# 40.net
KiCad netlist of a schematic drawn in Altium Designer
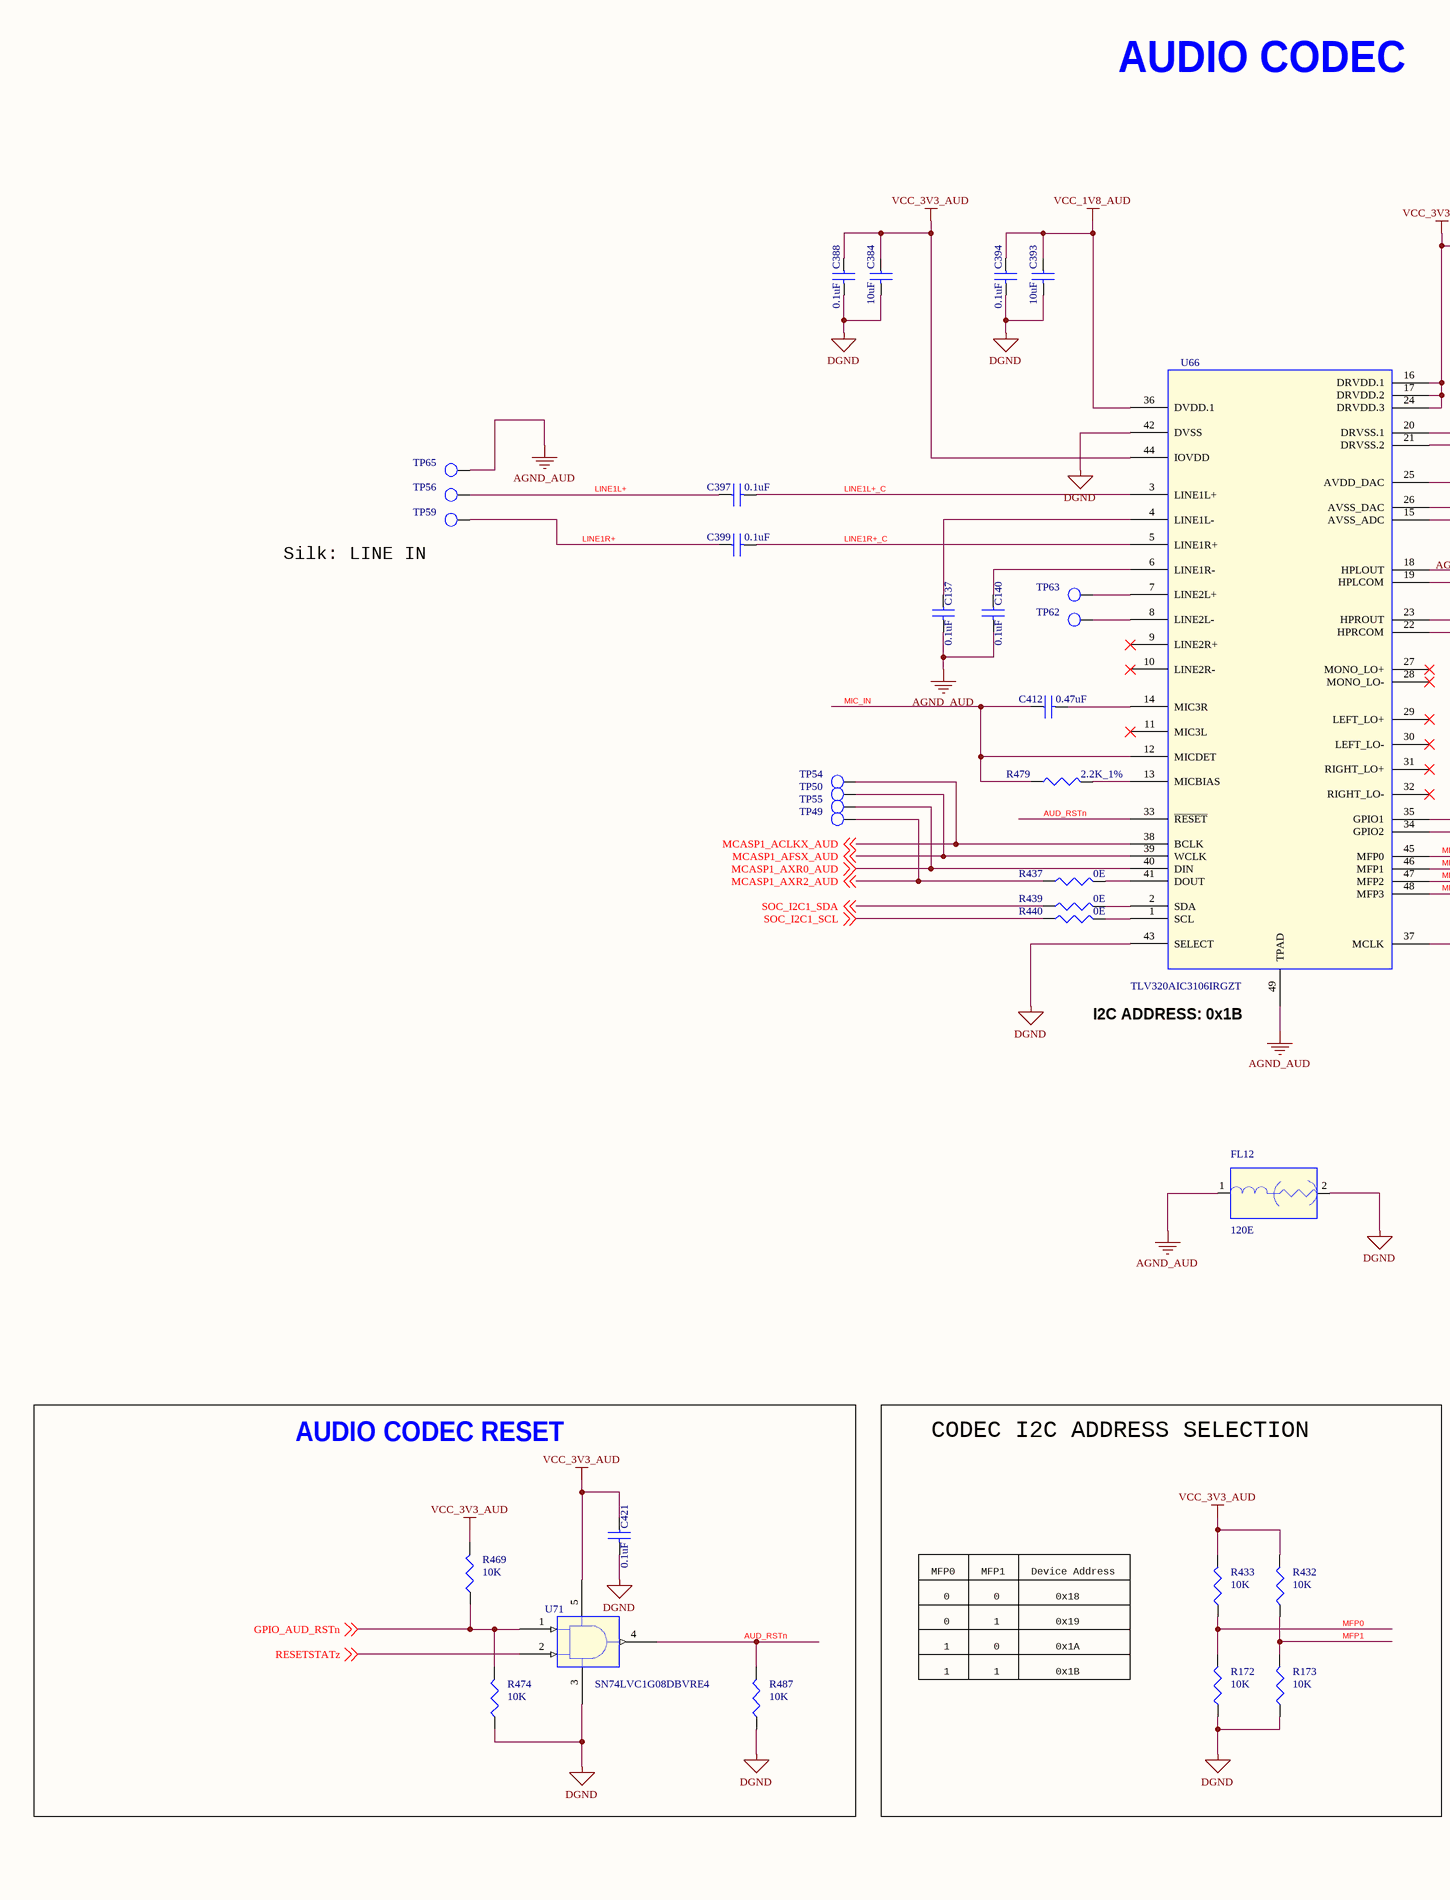
[diagram p0: 40.SchDoc, left]
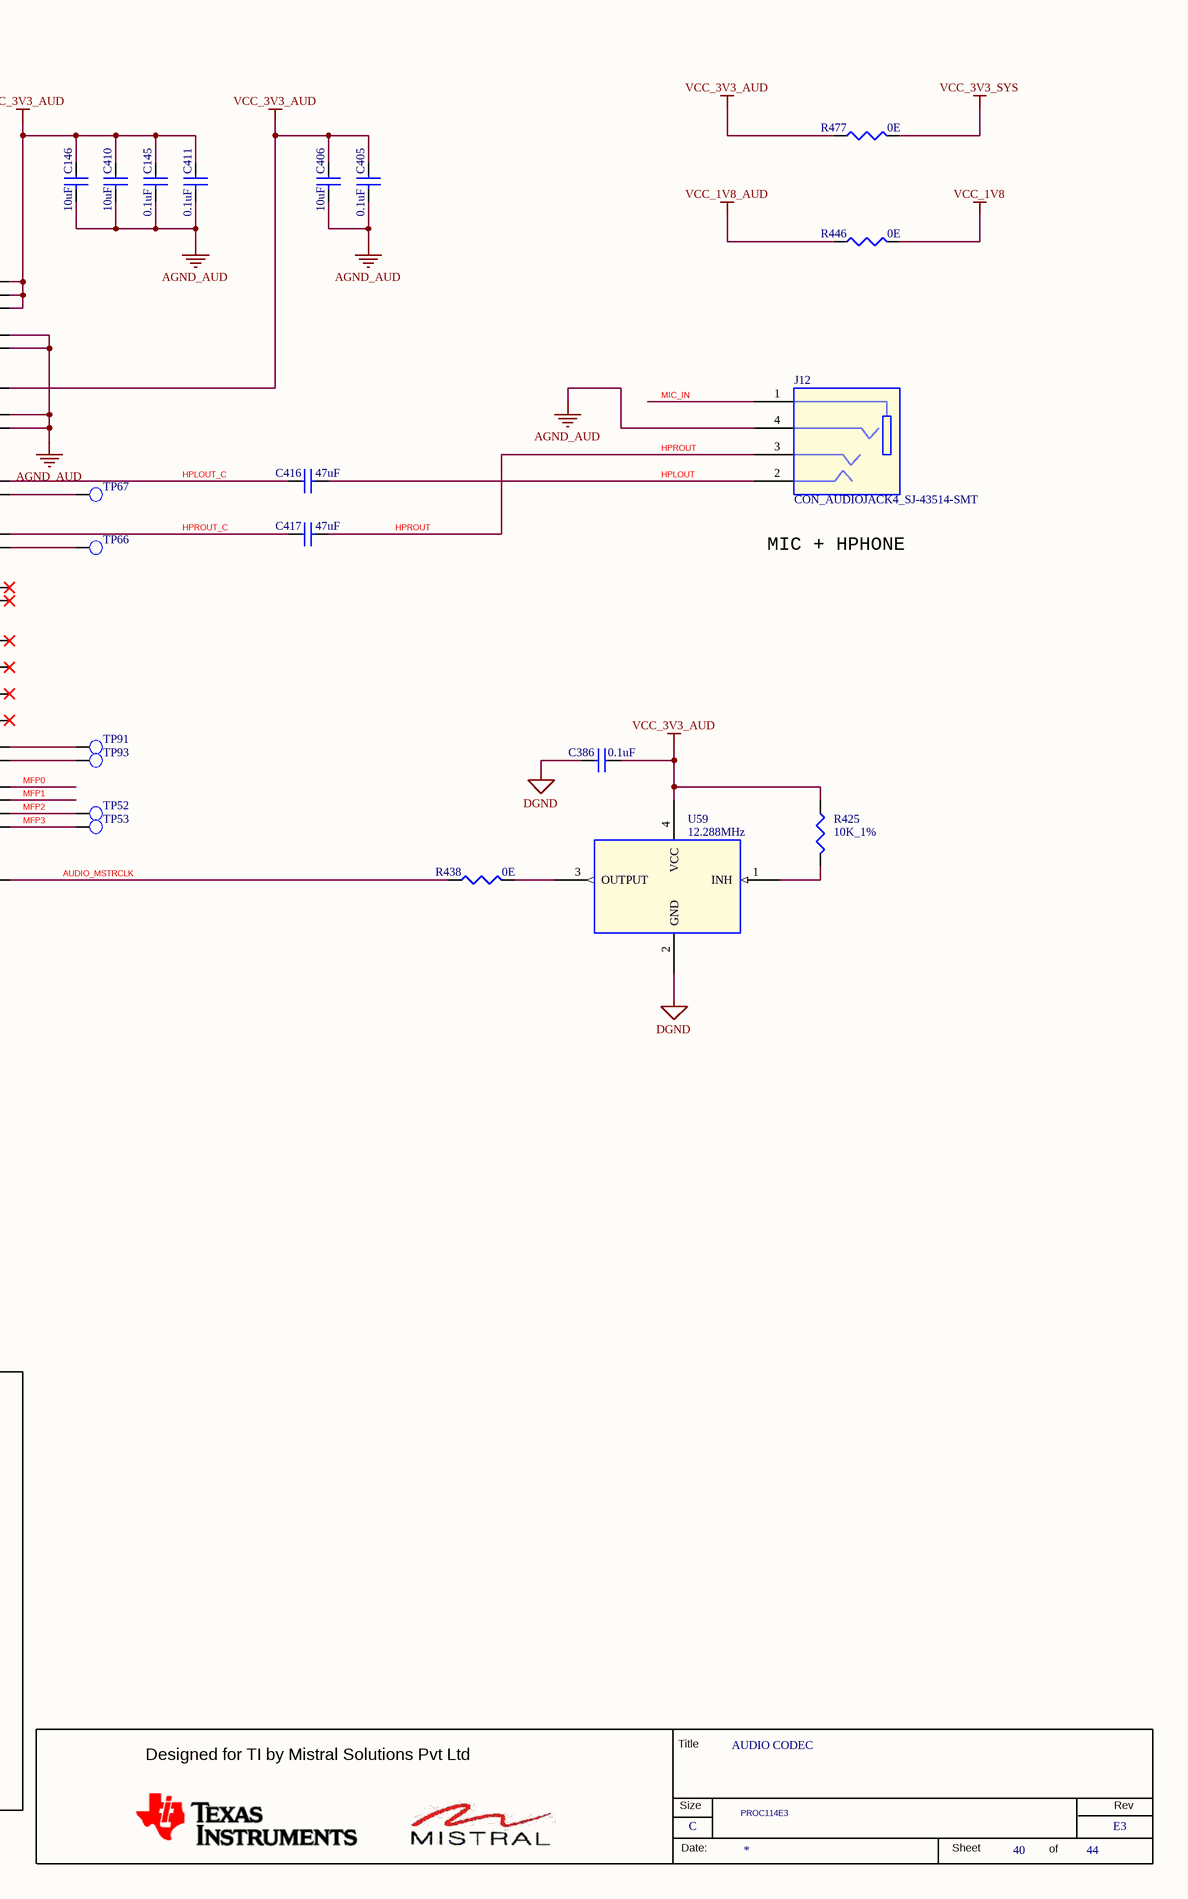
[diagram p1: 40.SchDoc, right]

(export (version "E")
  (design (tool "Eeschema 10.0.6"))
  (components
    (comp (ref "C137")
      (value "0.1uF")
      (footprint "CAP0201_0-5")
      (description "CAP CERAMIC 0.1uF 16V 10% X5R 0201")
      (fields (field (name "DISTRIBUTOR_PART_NUMBER") "490-14305-1-ND") (field (name "VOLTAGE") "16V"))
      (libsource (lib "*") (part "CAP_Dup2"))
    )
    (comp (ref "C140")
      (value "0.1uF")
      (footprint "CAP0201_0-5")
      (description "CAP CERAMIC 0.1uF 16V 10% X5R 0201")
      (fields (field (name "DISTRIBUTOR_PART_NUMBER") "490-14305-1-ND") (field (name "VOLTAGE") "16V"))
      (libsource (lib "*") (part "CAP_Dup2"))
    )
    (comp (ref "C145")
      (value "0.1uF")
      (footprint "CAP0201_0-5")
      (description "CAP CERAMIC 0.1uF 16V 10% X5R 0201")
      (fields
        (field (name "MISTRAL PART NO") "120009030072-R")
        (field (name "MFR_PART_NUMBER") "GRM033R61C104KE14D")
      )
      (libsource (lib "*") (part "CAP_Dup2"))
    )
    (comp (ref "C146")
      (value "10uF")
      (footprint "CAP0402_0-75")
      (description "CAP CERAMIC 10uF 10V 20% X5R 0402")
      (fields
        (field (name "DISTRIBUTOR_PART_NUMBER") "490-GRM155R61A106ME11DTR-ND")
        (field (name "VOLTAGE") "10V")
      )
      (libsource (lib "*") (part "CAP_Dup2"))
    )
    (comp (ref "C384")
      (value "10uF")
      (footprint "CAP0402_0-75")
      (description "CAP CERAMIC 10uF 10V 20% X5R 0402")
      (fields
        (field (name "DISTRIBUTOR_PART_NUMBER") "490-GRM155R61A106ME11DTR-ND")
        (field (name "VOLTAGE") "10V")
      )
      (libsource (lib "*") (part "CAP_Dup2"))
    )
    (comp (ref "C386")
      (value "0.1uF")
      (footprint "CAP0201_0-5")
      (description "CAP CERAMIC 0.1uF 16V 10% X5R 0201")
      (fields (field (name "DISTRIBUTOR_PART_NUMBER") "490-14305-1-ND") (field (name "VOLTAGE") "16V"))
      (libsource (lib "*") (part "CAP_Dup2"))
    )
    (comp (ref "C388")
      (value "0.1uF")
      (footprint "CAP0201_0-5")
      (description "CAP CERAMIC 0.1uF 16V 10% X5R 0201")
      (fields (field (name "DISTRIBUTOR_PART_NUMBER") "490-14305-1-ND") (field (name "VOLTAGE") "16V"))
      (libsource (lib "*") (part "CAP_Dup2"))
    )
    (comp (ref "C393")
      (value "10uF")
      (footprint "CAP0402_0-75")
      (description "CAP CERAMIC 10uF 10V 20% X5R 0402")
      (fields
        (field (name "DISTRIBUTOR_PART_NUMBER") "490-GRM155R61A106ME11DTR-ND")
        (field (name "VOLTAGE") "10V")
      )
      (libsource (lib "*") (part "CAP_Dup2"))
    )
    (comp (ref "C394")
      (value "0.1uF")
      (footprint "CAP0201_0-5")
      (description "CAP CERAMIC 0.1uF 16V 10% X5R 0201")
      (fields (field (name "DISTRIBUTOR_PART_NUMBER") "490-14305-1-ND") (field (name "VOLTAGE") "16V"))
      (libsource (lib "*") (part "CAP_Dup2"))
    )
    (comp (ref "C397")
      (value "0.1uF")
      (footprint "CAP0402_0-75")
      (description "CAP CERAMIC 0.1uF 50V 10% X7R 0402")
      (fields
        (field (name "MISTRAL PART NO") "120011100014-R")
        (field (name "MFR_PART_NUMBER") "GRM155R71H104KE14D")
      )
      (libsource (lib "*") (part "CAP_Dup2"))
    )
    (comp (ref "C399")
      (value "0.1uF")
      (footprint "CAP0402_0-75")
      (description "CAP CERAMIC 0.1uF 50V 10% X7R 0402")
      (fields (field (name "DISTRIBUTOR_PART_NUMBER") "490-10700-1-ND") (field (name "VOLTAGE") "50V"))
      (libsource (lib "*") (part "CAP_Dup2"))
    )
    (comp (ref "C405")
      (value "0.1uF")
      (footprint "CAP0201_0-5")
      (description "CAP CERAMIC 0.1uF 16V 10% X5R 0201")
      (fields (field (name "DISTRIBUTOR_PART_NUMBER") "490-14305-1-ND") (field (name "VOLTAGE") "16V"))
      (libsource (lib "*") (part "CAP_Dup2"))
    )
    (comp (ref "C406")
      (value "10uF")
      (footprint "CAP0402_0-75")
      (description "CAP CERAMIC 10uF 10V 20% X5R 0402")
      (fields
        (field (name "DISTRIBUTOR_PART_NUMBER") "490-GRM155R61A106ME11DTR-ND")
        (field (name "VOLTAGE") "10V")
      )
      (libsource (lib "*") (part "CAP_Dup2"))
    )
    (comp (ref "C410")
      (value "10uF")
      (footprint "CAP0402_0-75")
      (description "CAP CERAMIC 10uF 10V 20% X5R 0402")
      (fields
        (field (name "DISTRIBUTOR_PART_NUMBER") "490-GRM155R61A106ME11DTR-ND")
        (field (name "VOLTAGE") "10V")
      )
      (libsource (lib "*") (part "CAP_Dup2"))
    )
    (comp (ref "C411")
      (value "0.1uF")
      (footprint "CAP0201_0-5")
      (description "CAP CERAMIC 0.1uF 16V 10% X5R 0201")
      (fields (field (name "DISTRIBUTOR_PART_NUMBER") "490-14305-1-ND") (field (name "VOLTAGE") "16V"))
      (libsource (lib "*") (part "CAP_Dup2"))
    )
    (comp (ref "C412")
      (value "0.47uF")
      (footprint "CAP0402_0-75")
      (description "CAP CERAMIC 0.47uF 10V 10% X7R 0402")
      (fields (field (name "DISTRIBUTOR_PART_NUMBER") "490-14366-1-ND") (field (name "VOLTAGE") "10V"))
      (libsource (lib "*") (part "CAP_Dup2"))
    )
    (comp (ref "C416")
      (value "47uF")
      (footprint "CAP1206_2")
      (description "CAP CERAMIC 47uF 10V 20% X5R 1206")
      (fields (field (name "DISTRIBUTOR_PART_NUMBER") "490-5528-1-ND") (field (name "VOLTAGE") "10V"))
      (libsource (lib "*") (part "CAP_Dup2"))
    )
    (comp (ref "C417")
      (value "47uF")
      (footprint "CAP1206_2")
      (description "CAP CERAMIC 47uF 10V 20% X5R 1206")
      (fields (field (name "DISTRIBUTOR_PART_NUMBER") "490-5528-1-ND") (field (name "VOLTAGE") "10V"))
      (libsource (lib "*") (part "CAP_Dup2"))
    )
    (comp (ref "C421")
      (value "0.1uF")
      (footprint "CAP0402_0-75")
      (description "CAP CERAMIC 0.1uF 50V 10% X7R 0402")
      (fields
        (field (name "MISTRAL PART NO") "120011100014-R")
        (field (name "MFR_PART_NUMBER") "GRM155R71H104KE14D")
      )
      (libsource (lib "*") (part "CAP_Dup2"))
    )
    (comp (ref "FL12")
      (value "120E")
      (footprint "EMIFIL_BLM15A_0402_0-6")
      (description "IND FERRITE BEAD CHIP 120E 2A 0402")
      (fields
        (field (name "MISTRAL PART NO") "130013060022-R")
        (field (name "MFR_PART_NUMBER") "BLM15PX121SN1D")
      )
      (libsource (lib "*") (part "EMIFILTER_IND"))
    )
    (comp (ref "J12")
      (value "CON_AUDIOJACK4_SJ-43514-SMT")
      (footprint "CON_AV4_SJ-43514-SMT_S_R_S_5-1")
      (description "CON AUDIO JACK 4POS FEMALE RT SMD")
      (fields
        (field (name "MISTRAL PART NO") "150010060028-R")
        (field (name "MFR_PART_NUMBER") "SJ-43514-SMT-TR")
      )
      (libsource (lib "*") (part "CON_AUDIOJACK4_SJ-43514-SMT"))
    )
    (comp (ref "R172")
      (value "10K")
      (footprint "RES0201_0-5")
      (description "RES 10K 1/20W 5% 0201")
      (fields (field (name "DISTRIBUTOR_PART_NUMBER") "311-10KNCT-ND") (field (name "VOLTAGE") "NA"))
      (libsource (lib "*") (part "RESISTOR_Dup6"))
    )
    (comp (ref "R173")
      (value "10K")
      (footprint "RES0201_0-5")
      (description "RES 10K 1/20W 5% 0201")
      (fields (field (name "DISTRIBUTOR_PART_NUMBER") "311-10KNCT-ND") (field (name "VOLTAGE") "NA"))
      (libsource (lib "*") (part "RESISTOR_Dup6"))
    )
    (comp (ref "R425")
      (value "10K_1%")
      (footprint "RES0201_0-5")
      (description "RES 10K 1/20W 1% 0201")
      (fields
        (field (name "MISTRAL PART NO") "110011040018-R")
        (field (name "MFR_PART_NUMBER") "RC0201FR-0710KL")
      )
      (libsource (lib "*") (part "RESISTOR_Dup1"))
    )
    (comp (ref "R432")
      (value "10K")
      (footprint "RES0201_0-5")
      (description "RES 10K 1/20W 5% 0201")
      (fields (field (name "DISTRIBUTOR_PART_NUMBER") "311-10KNCT-ND") (field (name "VOLTAGE") "NA"))
      (libsource (lib "*") (part "RESISTOR_Dup6"))
    )
    (comp (ref "R433")
      (value "10K")
      (footprint "RES0201_0-5")
      (description "RES 10K 1/20W 5% 0201")
      (fields (field (name "DISTRIBUTOR_PART_NUMBER") "311-10KNCT-ND") (field (name "VOLTAGE") "NA"))
      (libsource (lib "*") (part "RESISTOR_Dup6"))
    )
    (comp (ref "R437")
      (value "0E")
      (footprint "RES0201_0-5")
      (description "RES 0E 1/20W 5% 0201")
      (fields (field (name "DISTRIBUTOR_PART_NUMBER") "311-0.0NCT-ND") (field (name "VOLTAGE") "NA"))
      (libsource (lib "*") (part "RESISTOR_Dup1"))
    )
    (comp (ref "R438")
      (value "0E")
      (footprint "RES0201_0-5")
      (description "RES 0E 1/20W 5% 0201")
      (fields (field (name "DISTRIBUTOR_PART_NUMBER") "311-0.0NCT-ND") (field (name "VOLTAGE") "NA"))
      (libsource (lib "*") (part "RESISTOR_Dup1"))
    )
    (comp (ref "R439")
      (value "0E")
      (footprint "RES0201_0-5")
      (description "RES 0E 1/20W 5% 0201")
      (fields (field (name "DISTRIBUTOR_PART_NUMBER") "311-0.0NCT-ND") (field (name "VOLTAGE") "NA"))
      (libsource (lib "*") (part "RESISTOR_Dup1"))
    )
    (comp (ref "R440")
      (value "0E")
      (footprint "RES0201_0-5")
      (description "RES 0E 1/20W 5% 0201")
      (fields (field (name "DISTRIBUTOR_PART_NUMBER") "311-0.0NCT-ND") (field (name "VOLTAGE") "NA"))
      (libsource (lib "*") (part "RESISTOR_Dup1"))
    )
    (comp (ref "R446")
      (value "0E")
      (footprint "RES0201_0-5")
      (description "RES 0E 1/20W 5% 0201")
      (fields (field (name "DISTRIBUTOR_PART_NUMBER") "311-0.0NCT-ND") (field (name "VOLTAGE") "NA"))
      (libsource (lib "*") (part "RESISTOR_Dup6"))
    )
    (comp (ref "R469")
      (value "10K")
      (footprint "RES0201_0-5")
      (description "RES 10K 1/20W 5% 0201")
      (fields (field (name "DISTRIBUTOR_PART_NUMBER") "311-10KNCT-ND") (field (name "VOLTAGE") "NA"))
      (libsource (lib "*") (part "RESISTOR_Dup1"))
    )
    (comp (ref "R474")
      (value "10K")
      (footprint "RES0201_0-5")
      (description "RES 10K 1/20W 5% 0201")
      (fields
        (field (name "MISTRAL PART NO") "110010070051-R")
        (field (name "MFR_PART_NUMBER") "RC0201JR-0710KL")
      )
      (libsource (lib "*") (part "RESISTOR_Dup1"))
    )
    (comp (ref "R477")
      (value "0E")
      (footprint "RES0201_0-5")
      (description "RES 0E 1/20W 5% 0201")
      (fields (field (name "DISTRIBUTOR_PART_NUMBER") "311-0.0NCT-ND") (field (name "VOLTAGE") "NA"))
      (libsource (lib "*") (part "RESISTOR_Dup6"))
    )
    (comp (ref "R479")
      (value "2.2K_1%")
      (footprint "RES0201_0-5")
      (description "RES 2.2K 1/20W 1% 0201")
      (fields
        (field (name "MISTRAL PART NO") "110017010016-R")
        (field (name "MFR_PART_NUMBER") "RC0201FR-072K2L")
      )
      (libsource (lib "*") (part "RESISTOR_Dup6"))
    )
    (comp (ref "R487")
      (value "10K")
      (footprint "RES0201_0-5")
      (description "RES 10K 1/20W 5% 0201")
      (fields
        (field (name "MISTRAL PART NO") "110010070051-R")
        (field (name "MFR_PART_NUMBER") "RC0201JR-0710KL")
      )
      (libsource (lib "*") (part "RESISTOR_Dup1"))
    )
    (comp (ref "TP49")
      (value "TP20_SMD")
      (footprint "TP20_SMD")
      (description "TESTPOINT CIR 20 SMD")
      (fields (field (name "MISTRAL PART NO") "NA"))
      (libsource (lib "*") (part "TESTPOINT"))
    )
    (comp (ref "TP50")
      (value "TP20_SMD")
      (footprint "TP20_SMD")
      (description "TESTPOINT CIR 20 SMD")
      (fields (field (name "VOLTAGE") "NA"))
      (libsource (lib "*") (part "TESTPOINT"))
    )
    (comp (ref "TP52")
      (value "TP20_SMD")
      (footprint "TP20_SMD")
      (description "TESTPOINT CIR 20 SMD")
      (fields (field (name "VOLTAGE") "NA"))
      (libsource (lib "*") (part "TESTPOINT"))
    )
    (comp (ref "TP53")
      (value "TP20_SMD")
      (footprint "TP20_SMD")
      (description "TESTPOINT CIR 20 SMD")
      (fields (field (name "VOLTAGE") "NA"))
      (libsource (lib "*") (part "TESTPOINT"))
    )
    (comp (ref "TP54")
      (value "TP20_SMD")
      (footprint "TP20_SMD")
      (description "TESTPOINT CIR 20 SMD")
      (fields (field (name "MISTRAL PART NO") "NA"))
      (libsource (lib "*") (part "TESTPOINT"))
    )
    (comp (ref "TP55")
      (value "TP20_SMD")
      (footprint "TP20_SMD")
      (description "TESTPOINT CIR 20 SMD")
      (fields (field (name "MISTRAL PART NO") "NA"))
      (libsource (lib "*") (part "TESTPOINT"))
    )
    (comp (ref "TP56")
      (value "THRU HOLE")
      (footprint "TP_40X65")
      (description "TESTPOINT 1.0MM DRILL PTH")
      (fields (field (name "MISTRAL PART NO") "130009030938") (field (name "MFR_PART_NUMBER") "TP_40X65"))
      (libsource (lib "*") (part "TESTPOINT"))
    )
    (comp (ref "TP59")
      (value "THRU HOLE")
      (footprint "TP_40X65")
      (description "TESTPOINT 1.0MM DRILL PTH")
      (fields (field (name "MISTRAL PART NO") "130009030938") (field (name "MFR_PART_NUMBER") "TP_40X65"))
      (libsource (lib "*") (part "TESTPOINT"))
    )
    (comp (ref "TP62")
      (value "TP20_SMD")
      (footprint "TP20_SMD")
      (description "TESTPOINT CIR 20 SMD")
      (fields (field (name "MISTRAL PART NO") "NA"))
      (libsource (lib "*") (part "TESTPOINT"))
    )
    (comp (ref "TP63")
      (value "TP20_SMD")
      (footprint "TP20_SMD")
      (description "TESTPOINT CIR 20 SMD")
      (fields (field (name "MISTRAL PART NO") "NA"))
      (libsource (lib "*") (part "TESTPOINT"))
    )
    (comp (ref "TP65")
      (value "THRU HOLE")
      (footprint "TP_40X65")
      (description "TESTPOINT 1.0MM DRILL PTH")
      (fields (field (name "DISTRIBUTOR_PART_NUMBER") "NA") (field (name "MFR_PART_NUMBER") "TP_40X65"))
      (libsource (lib "*") (part "TESTPOINT"))
    )
    (comp (ref "TP66")
      (value "TP20_SMD")
      (footprint "TP20_SMD")
      (description "TESTPOINT CIR 20 SMD")
      (fields (field (name "VOLTAGE") "NA"))
      (libsource (lib "*") (part "TESTPOINT"))
    )
    (comp (ref "TP67")
      (value "TP20_SMD")
      (footprint "TP20_SMD")
      (description "TESTPOINT CIR 20 SMD")
      (fields (field (name "VOLTAGE") "NA"))
      (libsource (lib "*") (part "TESTPOINT"))
    )
    (comp (ref "TP91")
      (value "TP20_SMD")
      (footprint "TP20_SMD")
      (description "TESTPOINT CIR 20 SMD")
      (fields (field (name "MISTRAL PART NO") "NA"))
      (libsource (lib "*") (part "TESTPOINT"))
    )
    (comp (ref "TP93")
      (value "TP20_SMD")
      (footprint "TP20_SMD")
      (description "TESTPOINT CIR 20 SMD")
      (fields (field (name "MISTRAL PART NO") "NA"))
      (libsource (lib "*") (part "TESTPOINT"))
    )
    (comp (ref "U59")
      (value "12.288MHz")
      (footprint "OSC4_KC2520B_100X80_SMD_0-8")
      (description "OSC 12.288MHz CMOS SMD")
      (fields
        (field (name "DISTRIBUTOR_PART_NUMBER") "1253-KC2520Z12.2880C1KX00CT-ND")
        (field (name "VOLTAGE") "NA")
      )
      (libsource (lib "*") (part "OSC_KC2016K"))
    )
    (comp (ref "U66")
      (value "TLV320AIC3106IRGZT")
      (footprint "VQFN48_19-68_285X285")
      (description "IC LOW-POWER STEREO AUDIO CODEC VQFN48")
      (fields
        (field (name "DISTRIBUTOR_PART_NUMBER") "TLV320AIC3106IRGZT-ND")
        (field (name "MISTRAL PART NO") "143010060003-R")
      )
      (libsource (lib "*") (part "TLV320AIC3106IRGZT_VQFN48"))
    )
    (comp (ref "U71")
      (value "SN74LVC1G08DBVRE4")
      (footprint "SOT23-5")
      (description "IC SINGLE 2-INPUT POSITIVE AND GATE SOT23-5")
      (fields
        (field (name "DISTRIBUTOR_PART_NUMBER") "SN74LVC1G08DBVRE4-ND")
        (field (name "MISTRAL PART NO") "141009060026-R")
      )
      (libsource (lib "*") (part "SN74LVC1G08DBVRE4_SOT23-5_Dup1"))
    )
  )
  (nets
    (net (code "1") (name "/AUDIO_MSTRCLK") (class "Default")
      (node (ref "R438") (pin "1") (pinfunction "1_1") (pintype "passive"))
      (node (ref "U66") (pin "37") (pinfunction "MCLK_37") (pintype "passive"))
    )
    (net (code "2") (name "/AUD_RSTn") (class "Default")
      (node (ref "R487") (pin "2") (pinfunction "2_2") (pintype "passive"))
      (node (ref "U66") (pin "33") (pinfunction "~{RESET}_33") (pintype "passive"))
      (node (ref "U71") (pin "4") (pinfunction "Y_4") (pintype "output"))
    )
    (net (code "3") (name "/HPLOUT") (class "Default")
      (node (ref "C416") (pin "2") (pinfunction "2_2") (pintype "passive"))
      (node (ref "J12") (pin "2") (pinfunction "2_2") (pintype "passive"))
    )
    (net (code "4") (name "/HPLOUT_C") (class "Default")
      (node (ref "C416") (pin "1") (pinfunction "1_1") (pintype "passive"))
      (node (ref "U66") (pin "18") (pinfunction "HPLOUT_18") (pintype "passive"))
    )
    (net (code "5") (name "/HPROUT") (class "Default")
      (node (ref "C417") (pin "2") (pinfunction "2_2") (pintype "passive"))
      (node (ref "J12") (pin "3") (pinfunction "3_3") (pintype "passive"))
    )
    (net (code "6") (name "/HPROUT_C") (class "Default")
      (node (ref "C417") (pin "1") (pinfunction "1_1") (pintype "passive"))
      (node (ref "U66") (pin "23") (pinfunction "HPROUT_23") (pintype "passive"))
    )
    (net (code "7") (name "/LINE1L+") (class "Default")
      (node (ref "C397") (pin "1") (pinfunction "1_1") (pintype "passive"))
      (node (ref "TP56") (pin "1") (pinfunction "TP_1") (pintype "passive"))
    )
    (net (code "8") (name "/LINE1L+_C") (class "Default")
      (node (ref "C397") (pin "2") (pinfunction "2_2") (pintype "passive"))
      (node (ref "U66") (pin "3") (pinfunction "LINE1L+_3") (pintype "passive"))
    )
    (net (code "9") (name "/LINE1R+") (class "Default")
      (node (ref "C399") (pin "1") (pinfunction "1_1") (pintype "passive"))
      (node (ref "TP59") (pin "1") (pinfunction "TP_1") (pintype "passive"))
    )
    (net (code "10") (name "/LINE1R+_C") (class "Default")
      (node (ref "C399") (pin "2") (pinfunction "2_2") (pintype "passive"))
      (node (ref "U66") (pin "5") (pinfunction "LINE1R+_5") (pintype "passive"))
    )
    (net (code "11") (name "/MFP0") (class "Default")
      (node (ref "R172") (pin "1") (pinfunction "1_1") (pintype "passive"))
      (node (ref "R433") (pin "2") (pinfunction "2_2") (pintype "passive"))
      (node (ref "U66") (pin "45") (pinfunction "MFP0_45") (pintype "passive"))
    )
    (net (code "12") (name "/MFP1") (class "Default")
      (node (ref "R173") (pin "1") (pinfunction "1_1") (pintype "passive"))
      (node (ref "R432") (pin "2") (pinfunction "2_2") (pintype "passive"))
      (node (ref "U66") (pin "46") (pinfunction "MFP1_46") (pintype "passive"))
    )
    (net (code "13") (name "/MFP2") (class "Default")
      (node (ref "TP52") (pin "1") (pinfunction "TP_1") (pintype "passive"))
      (node (ref "U66") (pin "47") (pinfunction "MFP2_47") (pintype "passive"))
    )
    (net (code "14") (name "/MFP3") (class "Default")
      (node (ref "TP53") (pin "1") (pinfunction "TP_1") (pintype "passive"))
      (node (ref "U66") (pin "48") (pinfunction "MFP3_48") (pintype "passive"))
    )
    (net (code "15") (name "/MIC_IN") (class "Default")
      (node (ref "C412") (pin "1") (pinfunction "1_1") (pintype "passive"))
      (node (ref "J12") (pin "1") (pinfunction "1_1") (pintype "passive"))
      (node (ref "R479") (pin "1") (pinfunction "1_1") (pintype "passive"))
      (node (ref "U66") (pin "12") (pinfunction "MICDET_12") (pintype "passive"))
    )
    (net (code "16") (name "AGND_AUD") (class "Default")
      (node (ref "C137") (pin "2") (pinfunction "2_2") (pintype "passive"))
      (node (ref "C140") (pin "2") (pinfunction "2_2") (pintype "passive"))
      (node (ref "C145") (pin "2") (pinfunction "2_2") (pintype "passive"))
      (node (ref "C146") (pin "2") (pinfunction "2_2") (pintype "passive"))
      (node (ref "C405") (pin "2") (pinfunction "2_2") (pintype "passive"))
      (node (ref "C406") (pin "2") (pinfunction "2_2") (pintype "passive"))
      (node (ref "C410") (pin "2") (pinfunction "2_2") (pintype "passive"))
      (node (ref "C411") (pin "2") (pinfunction "2_2") (pintype "passive"))
      (node (ref "FL12") (pin "1") (pinfunction "1_1") (pintype "passive"))
      (node (ref "J12") (pin "4") (pinfunction "4_4") (pintype "passive"))
      (node (ref "TP65") (pin "1") (pinfunction "TP_1") (pintype "passive"))
      (node (ref "U66") (pin "15") (pinfunction "AVSS_ADC_15") (pintype "passive"))
      (node (ref "U66") (pin "20") (pinfunction "DRVSS.1_20") (pintype "passive"))
      (node (ref "U66") (pin "21") (pinfunction "DRVSS.2_21") (pintype "passive"))
      (node (ref "U66") (pin "26") (pinfunction "AVSS_DAC_26") (pintype "passive"))
      (node (ref "U66") (pin "49") (pinfunction "TPAD_49") (pintype "passive"))
    )
    (net (code "17") (name "DGND") (class "Default")
      (node (ref "C384") (pin "2") (pinfunction "2_2") (pintype "passive"))
      (node (ref "C386") (pin "2") (pinfunction "2_2") (pintype "passive"))
      (node (ref "C388") (pin "2") (pinfunction "2_2") (pintype "passive"))
      (node (ref "C393") (pin "2") (pinfunction "2_2") (pintype "passive"))
      (node (ref "C394") (pin "2") (pinfunction "2_2") (pintype "passive"))
      (node (ref "C421") (pin "2") (pinfunction "2_2") (pintype "passive"))
      (node (ref "FL12") (pin "2") (pinfunction "2_2") (pintype "passive"))
      (node (ref "R172") (pin "2") (pinfunction "2_2") (pintype "passive"))
      (node (ref "R173") (pin "2") (pinfunction "2_2") (pintype "passive"))
      (node (ref "R474") (pin "1") (pinfunction "1_1") (pintype "passive"))
      (node (ref "R487") (pin "1") (pinfunction "1_1") (pintype "passive"))
      (node (ref "U59") (pin "2") (pinfunction "GND_2") (pintype "power_in"))
      (node (ref "U66") (pin "42") (pinfunction "DVSS_42") (pintype "passive"))
      (node (ref "U66") (pin "43") (pinfunction "SELECT_43") (pintype "passive"))
      (node (ref "U71") (pin "3") (pinfunction "GND_3") (pintype "power_in"))
    )
    (net (code "18") (name "GPIO_AUD_RSTn") (class "Default")
      (node (ref "R469") (pin "1") (pinfunction "1_1") (pintype "passive"))
      (node (ref "R474") (pin "2") (pinfunction "2_2") (pintype "passive"))
      (node (ref "U71") (pin "1") (pinfunction "A_1") (pintype "input"))
    )
    (net (code "19") (name "MCASP1_ACLKX_AUD") (class "Default")
      (node (ref "TP54") (pin "1") (pinfunction "TP_1") (pintype "passive"))
      (node (ref "U66") (pin "38") (pinfunction "BCLK_38") (pintype "passive"))
    )
    (net (code "20") (name "MCASP1_AFSX_AUD") (class "Default")
      (node (ref "TP50") (pin "1") (pinfunction "TP_1") (pintype "passive"))
      (node (ref "U66") (pin "39") (pinfunction "WCLK_39") (pintype "passive"))
    )
    (net (code "21") (name "MCASP1_AXR0_AUD") (class "Default")
      (node (ref "TP55") (pin "1") (pinfunction "TP_1") (pintype "passive"))
      (node (ref "U66") (pin "40") (pinfunction "DIN_40") (pintype "passive"))
    )
    (net (code "22") (name "MCASP1_AXR2_AUD") (class "Default")
      (node (ref "R437") (pin "1") (pinfunction "1_1") (pintype "passive"))
      (node (ref "TP49") (pin "1") (pinfunction "TP_1") (pintype "passive"))
    )
    (net (code "23") (name "Net-(TP62-TP)") (class "Default")
      (node (ref "TP62") (pin "1") (pinfunction "TP_1") (pintype "passive"))
      (node (ref "U66") (pin "8") (pinfunction "LINE2L-_8") (pintype "passive"))
    )
    (net (code "24") (name "Net-(TP63-TP)") (class "Default")
      (node (ref "TP63") (pin "1") (pinfunction "TP_1") (pintype "passive"))
      (node (ref "U66") (pin "7") (pinfunction "LINE2L+_7") (pintype "passive"))
    )
    (net (code "25") (name "Net-(TP66-TP)") (class "Default")
      (node (ref "TP66") (pin "1") (pinfunction "TP_1") (pintype "passive"))
      (node (ref "U66") (pin "22") (pinfunction "HPRCOM_22") (pintype "passive"))
    )
    (net (code "26") (name "Net-(TP67-TP)") (class "Default")
      (node (ref "TP67") (pin "1") (pinfunction "TP_1") (pintype "passive"))
      (node (ref "U66") (pin "19") (pinfunction "HPLCOM_19") (pintype "passive"))
    )
    (net (code "27") (name "Net-(TP91-TP)") (class "Default")
      (node (ref "TP91") (pin "1") (pinfunction "TP_1") (pintype "passive"))
      (node (ref "U66") (pin "35") (pinfunction "GPIO1_35") (pintype "passive"))
    )
    (net (code "28") (name "Net-(TP93-TP)") (class "Default")
      (node (ref "TP93") (pin "1") (pinfunction "TP_1") (pintype "passive"))
      (node (ref "U66") (pin "34") (pinfunction "GPIO2_34") (pintype "passive"))
    )
    (net (code "29") (name "Net-(U59-INH)") (class "Default")
      (node (ref "R425") (pin "2") (pinfunction "2_2") (pintype "passive"))
      (node (ref "U59") (pin "1") (pinfunction "INH_1") (pintype "input"))
    )
    (net (code "30") (name "Net-(U59-OUTPUT)") (class "Default")
      (node (ref "R438") (pin "2") (pinfunction "2_2") (pintype "passive"))
      (node (ref "U59") (pin "3") (pinfunction "OUTPUT_3") (pintype "output"))
    )
    (net (code "31") (name "Net-(U66-DOUT)") (class "Default")
      (node (ref "R437") (pin "2") (pinfunction "2_2") (pintype "passive"))
      (node (ref "U66") (pin "41") (pinfunction "DOUT_41") (pintype "passive"))
    )
    (net (code "32") (name "Net-(U66-LINE1L-)") (class "Default")
      (node (ref "C137") (pin "1") (pinfunction "1_1") (pintype "passive"))
      (node (ref "U66") (pin "4") (pinfunction "LINE1L-_4") (pintype "passive"))
    )
    (net (code "33") (name "Net-(U66-LINE1R-)") (class "Default")
      (node (ref "C140") (pin "1") (pinfunction "1_1") (pintype "passive"))
      (node (ref "U66") (pin "6") (pinfunction "LINE1R-_6") (pintype "passive"))
    )
    (net (code "34") (name "Net-(U66-MIC3R)") (class "Default")
      (node (ref "C412") (pin "2") (pinfunction "2_2") (pintype "passive"))
      (node (ref "U66") (pin "14") (pinfunction "MIC3R_14") (pintype "passive"))
    )
    (net (code "35") (name "Net-(U66-MICBIAS)") (class "Default")
      (node (ref "R479") (pin "2") (pinfunction "2_2") (pintype "passive"))
      (node (ref "U66") (pin "13") (pinfunction "MICBIAS_13") (pintype "passive"))
    )
    (net (code "36") (name "Net-(U66-SCL)") (class "Default")
      (node (ref "R440") (pin "2") (pinfunction "2_2") (pintype "passive"))
      (node (ref "U66") (pin "1") (pinfunction "SCL_1") (pintype "passive"))
    )
    (net (code "37") (name "Net-(U66-SDA)") (class "Default")
      (node (ref "R439") (pin "2") (pinfunction "2_2") (pintype "passive"))
      (node (ref "U66") (pin "2") (pinfunction "SDA_2") (pintype "passive"))
    )
    (net (code "38") (name "RESETSTATz") (class "Default")
      (node (ref "U71") (pin "2") (pinfunction "B_2") (pintype "input"))
    )
    (net (code "39") (name "SOC_I2C1_SCL") (class "Default")
      (node (ref "R440") (pin "1") (pinfunction "1_1") (pintype "passive"))
    )
    (net (code "40") (name "SOC_I2C1_SDA") (class "Default")
      (node (ref "R439") (pin "1") (pinfunction "1_1") (pintype "passive"))
    )
    (net (code "41") (name "VCC_1V8") (class "Default")
      (node (ref "R446") (pin "2") (pinfunction "2_2") (pintype "passive"))
    )
    (net (code "42") (name "VCC_1V8_AUD") (class "Default")
      (node (ref "C393") (pin "1") (pinfunction "1_1") (pintype "passive"))
      (node (ref "C394") (pin "1") (pinfunction "1_1") (pintype "passive"))
      (node (ref "R446") (pin "1") (pinfunction "1_1") (pintype "passive"))
      (node (ref "U66") (pin "36") (pinfunction "DVDD.1_36") (pintype "passive"))
    )
    (net (code "43") (name "VCC_3V3_AUD") (class "Default")
      (node (ref "C145") (pin "1") (pinfunction "1_1") (pintype "passive"))
      (node (ref "C146") (pin "1") (pinfunction "1_1") (pintype "passive"))
      (node (ref "C384") (pin "1") (pinfunction "1_1") (pintype "passive"))
      (node (ref "C386") (pin "1") (pinfunction "1_1") (pintype "passive"))
      (node (ref "C388") (pin "1") (pinfunction "1_1") (pintype "passive"))
      (node (ref "C405") (pin "1") (pinfunction "1_1") (pintype "passive"))
      (node (ref "C406") (pin "1") (pinfunction "1_1") (pintype "passive"))
      (node (ref "C410") (pin "1") (pinfunction "1_1") (pintype "passive"))
      (node (ref "C411") (pin "1") (pinfunction "1_1") (pintype "passive"))
      (node (ref "C421") (pin "1") (pinfunction "1_1") (pintype "passive"))
      (node (ref "R425") (pin "1") (pinfunction "1_1") (pintype "passive"))
      (node (ref "R432") (pin "1") (pinfunction "1_1") (pintype "passive"))
      (node (ref "R433") (pin "1") (pinfunction "1_1") (pintype "passive"))
      (node (ref "R469") (pin "2") (pinfunction "2_2") (pintype "passive"))
      (node (ref "R477") (pin "1") (pinfunction "1_1") (pintype "passive"))
      (node (ref "U59") (pin "4") (pinfunction "VCC_4") (pintype "power_in"))
      (node (ref "U66") (pin "16") (pinfunction "DRVDD.1_16") (pintype "passive"))
      (node (ref "U66") (pin "17") (pinfunction "DRVDD.2_17") (pintype "passive"))
      (node (ref "U66") (pin "24") (pinfunction "DRVDD.3_24") (pintype "passive"))
      (node (ref "U66") (pin "25") (pinfunction "AVDD_DAC_25") (pintype "passive"))
      (node (ref "U66") (pin "44") (pinfunction "IOVDD_44") (pintype "passive"))
      (node (ref "U71") (pin "5") (pinfunction "VCC_5") (pintype "power_in"))
    )
    (net (code "44") (name "VCC_3V3_SYS") (class "Default")
      (node (ref "R477") (pin "2") (pinfunction "2_2") (pintype "passive"))
    )
    (net (code "45") (name "unconnected-(U66-LEFT_LO+-Pad29)") (class "Default")
      (node (ref "U66") (pin "29") (pinfunction "LEFT_LO+_29") (pintype "passive+no_connect"))
    )
    (net (code "46") (name "unconnected-(U66-LEFT_LO--Pad30)") (class "Default")
      (node (ref "U66") (pin "30") (pinfunction "LEFT_LO-_30") (pintype "passive+no_connect"))
    )
    (net (code "47") (name "unconnected-(U66-LINE2R+-Pad9)") (class "Default")
      (node (ref "U66") (pin "9") (pinfunction "LINE2R+_9") (pintype "passive+no_connect"))
    )
    (net (code "48") (name "unconnected-(U66-LINE2R--Pad10)") (class "Default")
      (node (ref "U66") (pin "10") (pinfunction "LINE2R-_10") (pintype "passive+no_connect"))
    )
    (net (code "49") (name "unconnected-(U66-MIC3L-Pad11)") (class "Default")
      (node (ref "U66") (pin "11") (pinfunction "MIC3L_11") (pintype "passive+no_connect"))
    )
    (net (code "50") (name "unconnected-(U66-MONO_LO+-Pad27)") (class "Default")
      (node (ref "U66") (pin "27") (pinfunction "MONO_LO+_27") (pintype "passive+no_connect"))
    )
    (net (code "51") (name "unconnected-(U66-MONO_LO--Pad28)") (class "Default")
      (node (ref "U66") (pin "28") (pinfunction "MONO_LO-_28") (pintype "passive+no_connect"))
    )
    (net (code "52") (name "unconnected-(U66-RIGHT_LO+-Pad31)") (class "Default")
      (node (ref "U66") (pin "31") (pinfunction "RIGHT_LO+_31") (pintype "passive+no_connect"))
    )
    (net (code "53") (name "unconnected-(U66-RIGHT_LO--Pad32)") (class "Default")
      (node (ref "U66") (pin "32") (pinfunction "RIGHT_LO-_32") (pintype "passive+no_connect"))
    )
  )
)
